# Quadcopter.net
KiCad netlist of a schematic drawn in Altium Designer
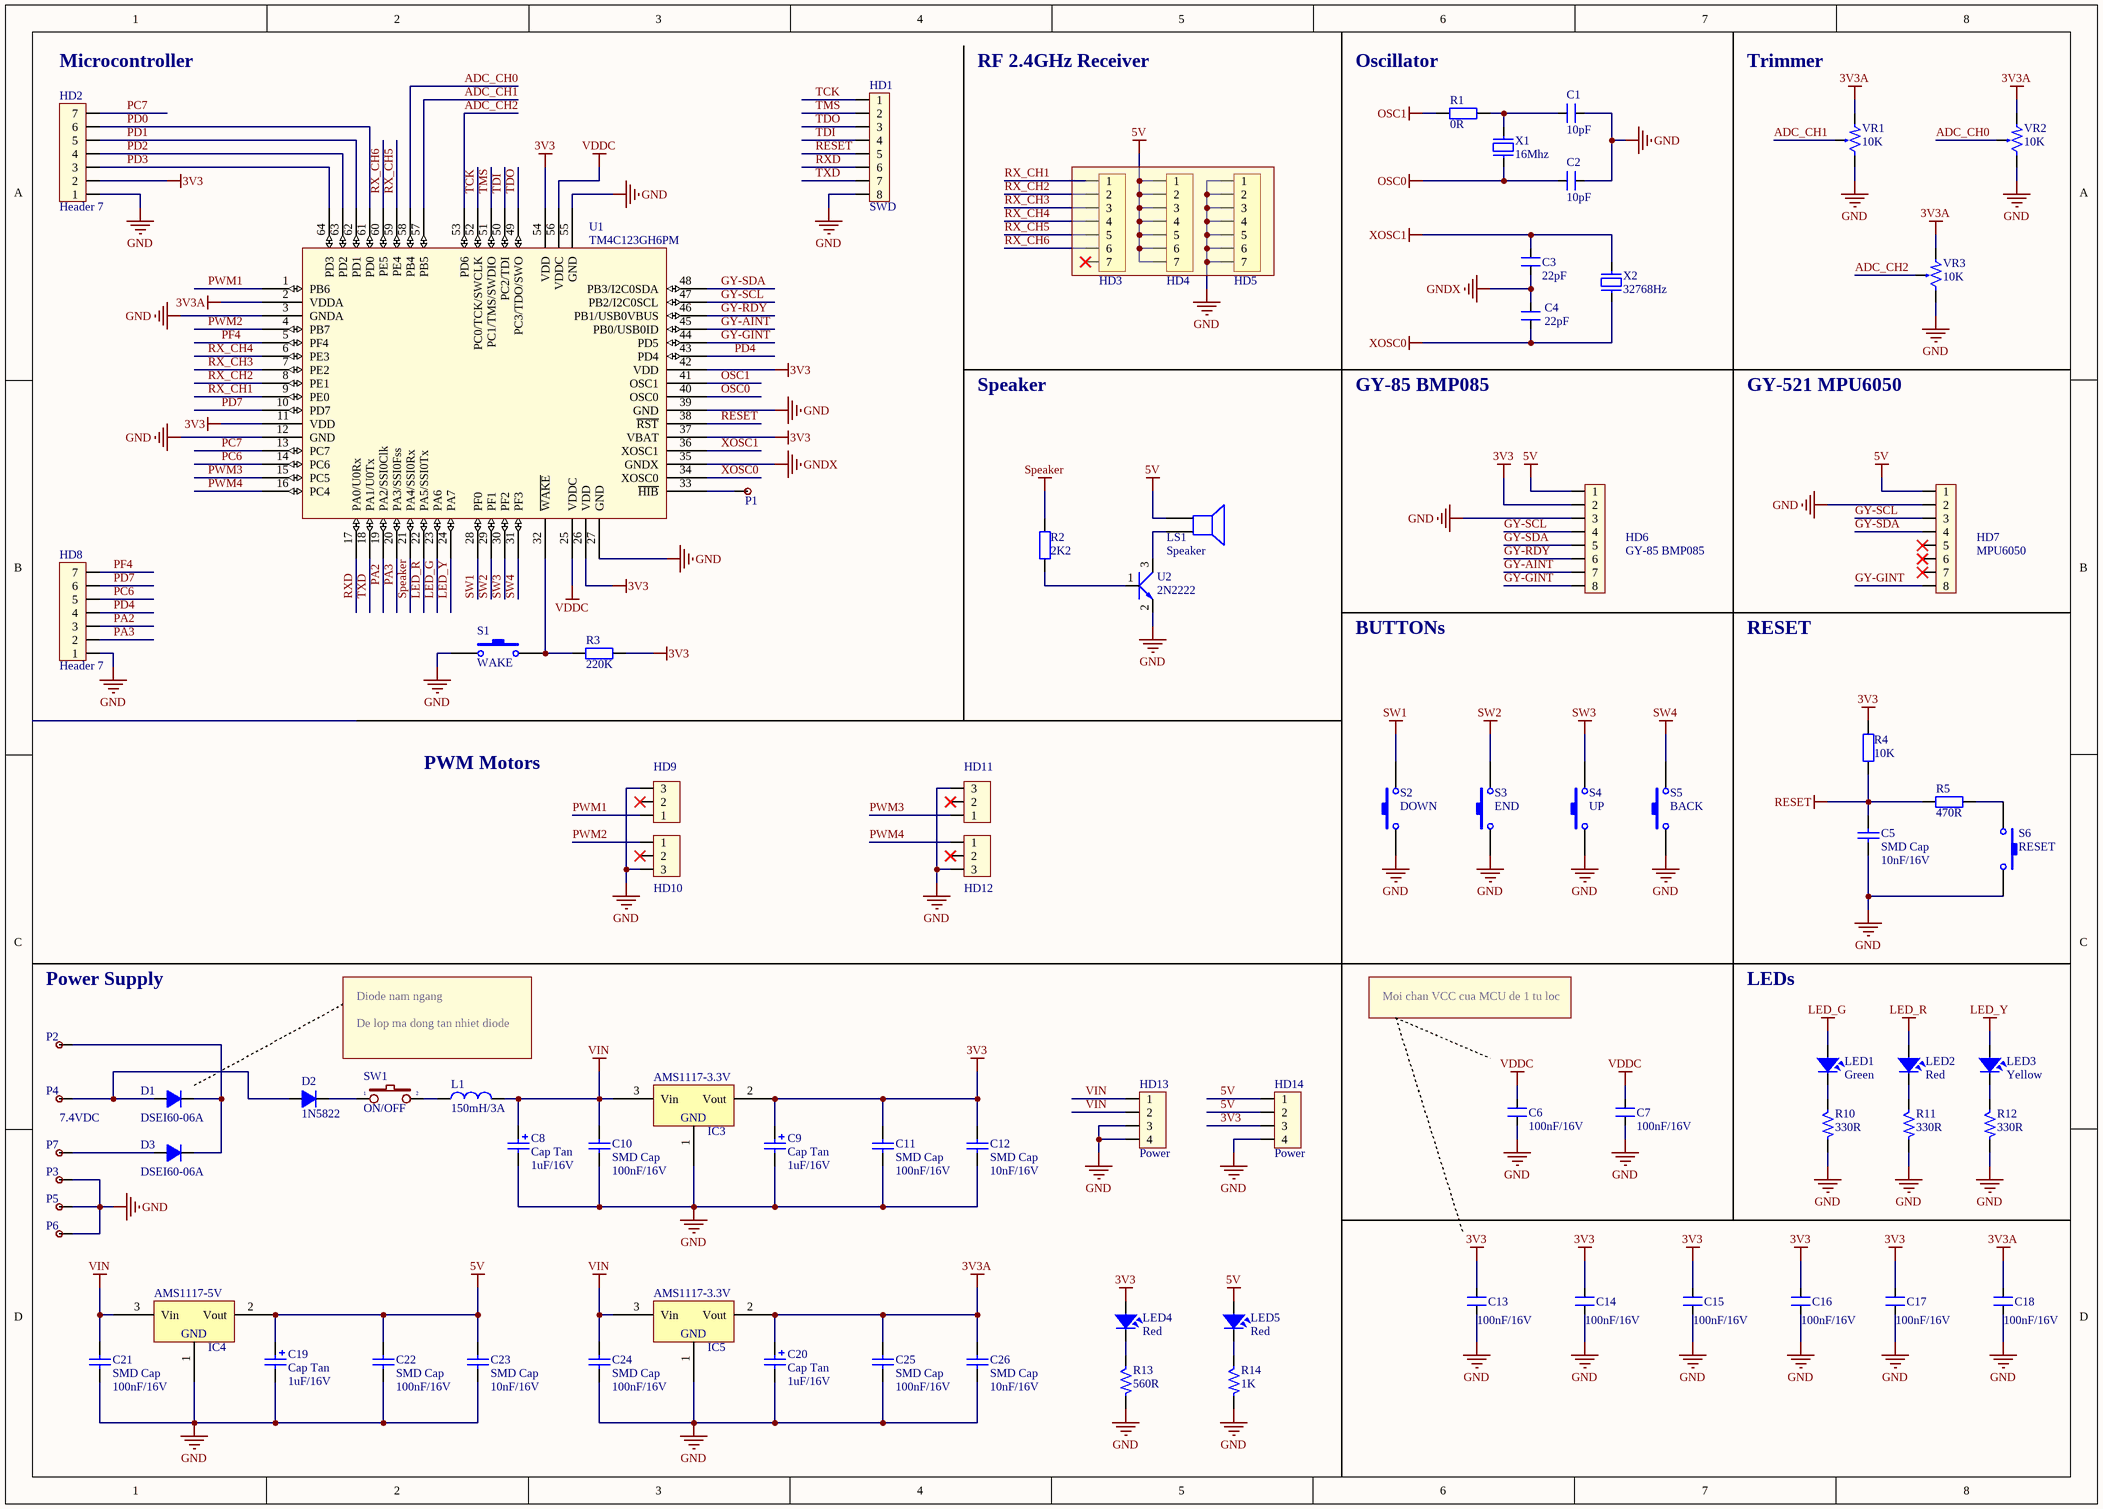
[diagram p0: Quadcopter.schdoc]

(export (version "E")
  (design (tool "Eeschema 10.0.6"))
  (components
    (comp (ref "C1")
      (value "10pF")
      (footprint "C0603")
      (description "0805-SMD Capacitor")
      (libsource (lib "syhaunguyen") (part "CN1"))
    )
    (comp (ref "C2")
      (value "10pF")
      (footprint "C0603")
      (description "0805-SMD Capacitor")
      (libsource (lib "syhaunguyen") (part "CN1"))
    )
    (comp (ref "C3")
      (value "22pF")
      (footprint "C0603")
      (description "0805-SMD Capacitor")
      (libsource (lib "syhaunguyen") (part "CN1"))
    )
    (comp (ref "C4")
      (value "22pF")
      (footprint "C0603")
      (description "0805-SMD Capacitor")
      (libsource (lib "syhaunguyen") (part "CN1"))
    )
    (comp (ref "C5")
      (value "SMD Cap")
      (footprint "C0603")
      (description "0805-10nF-50V Cap")
      (fields (field (name "ALTIUM_VALUE") "10nF/16V"))
      (libsource (lib "Miscellaneous Devices") (part "Cap"))
    )
    (comp (ref "C6")
      (value "100nF/16V")
      (footprint "C0603")
      (description "0805-SMD Capacitor")
      (fields (field (name "Comment") "SMD Cap"))
      (libsource (lib "syhaunguyen") (part "CN1"))
    )
    (comp (ref "C7")
      (value "100nF/16V")
      (footprint "C0603")
      (description "0805-SMD Capacitor")
      (fields (field (name "Comment") "SMD Cap"))
      (libsource (lib "syhaunguyen") (part "CN1"))
    )
    (comp (ref "C8")
      (value "Cap Tan")
      (footprint "CAP_TANTA_1uF_16V")
      (description "Cap Tantalum")
      (fields (field (name "ALTIUM_VALUE") "1uF/16V"))
      (libsource (lib "PassiveComponents_Sau") (part "Cap Pol2"))
    )
    (comp (ref "C9")
      (value "Cap Tan")
      (footprint "CAP_TANTA_1uF_16V")
      (description "Cap Tantalum")
      (fields (field (name "ALTIUM_VALUE") "1uF/16V"))
      (libsource (lib "PassiveComponents_Sau") (part "Cap Pol2"))
    )
    (comp (ref "C10")
      (value "SMD Cap")
      (footprint "C0603")
      (description "SMD Capacitor")
      (fields (field (name "ALTIUM_VALUE") "100nF/16V"))
      (libsource (lib "PassiveComponents_Sau") (part "Cap Cera"))
    )
    (comp (ref "C11")
      (value "SMD Cap")
      (footprint "C0603")
      (description "SMD Capacitor")
      (fields (field (name "ALTIUM_VALUE") "100nF/16V"))
      (libsource (lib "PassiveComponents_Sau") (part "Cap Cera"))
    )
    (comp (ref "C12")
      (value "SMD Cap")
      (footprint "C0603")
      (description "SMD Capacitor")
      (fields (field (name "ALTIUM_VALUE") "10nF/16V"))
      (libsource (lib "PassiveComponents_Sau") (part "Cap Cera"))
    )
    (comp (ref "C13")
      (value "100nF/16V")
      (footprint "C0603")
      (description "0805-SMD Capacitor")
      (fields (field (name "Comment") "SMD Cap"))
      (libsource (lib "syhaunguyen") (part "CN1"))
    )
    (comp (ref "C14")
      (value "100nF/16V")
      (footprint "C0603")
      (description "0805-SMD Capacitor")
      (fields (field (name "Comment") "SMD Cap"))
      (libsource (lib "syhaunguyen") (part "CN1"))
    )
    (comp (ref "C15")
      (value "100nF/16V")
      (footprint "C0603")
      (description "0805-SMD Capacitor")
      (fields (field (name "Comment") "SMD Cap"))
      (libsource (lib "syhaunguyen") (part "CN1"))
    )
    (comp (ref "C16")
      (value "100nF/16V")
      (footprint "C0603")
      (description "0805-SMD Capacitor")
      (fields (field (name "Comment") "SMD Cap"))
      (libsource (lib "syhaunguyen") (part "CN1"))
    )
    (comp (ref "C17")
      (value "100nF/16V")
      (footprint "C0603")
      (description "0805-SMD Capacitor")
      (fields (field (name "Comment") "SMD Cap"))
      (libsource (lib "syhaunguyen") (part "CN1"))
    )
    (comp (ref "C18")
      (value "100nF/16V")
      (footprint "C0603")
      (description "0805-SMD Capacitor")
      (fields (field (name "Comment") "SMD Cap"))
      (libsource (lib "syhaunguyen") (part "CN1"))
    )
    (comp (ref "C19")
      (value "Cap Tan")
      (footprint "CAP_TANTA_1uF_16V")
      (description "Cap Tantalum")
      (fields (field (name "ALTIUM_VALUE") "1uF/16V"))
      (libsource (lib "PassiveComponents_Sau") (part "Cap Pol2"))
    )
    (comp (ref "C20")
      (value "Cap Tan")
      (footprint "CAP_TANTA_1uF_16V")
      (description "Cap Tantalum")
      (fields (field (name "ALTIUM_VALUE") "1uF/16V"))
      (libsource (lib "PassiveComponents_Sau") (part "Cap Pol2"))
    )
    (comp (ref "C21")
      (value "SMD Cap")
      (footprint "C0603")
      (description "SMD Capacitor")
      (fields (field (name "ALTIUM_VALUE") "100nF/16V"))
      (libsource (lib "PassiveComponents_Sau") (part "Cap Cera"))
    )
    (comp (ref "C22")
      (value "SMD Cap")
      (footprint "C0603")
      (description "SMD Capacitor")
      (fields (field (name "ALTIUM_VALUE") "100nF/16V"))
      (libsource (lib "PassiveComponents_Sau") (part "Cap Cera"))
    )
    (comp (ref "C23")
      (value "SMD Cap")
      (footprint "C0603")
      (description "SMD Capacitor")
      (fields (field (name "ALTIUM_VALUE") "10nF/16V"))
      (libsource (lib "PassiveComponents_Sau") (part "Cap Cera"))
    )
    (comp (ref "C24")
      (value "SMD Cap")
      (footprint "C0603")
      (description "SMD Capacitor")
      (fields (field (name "ALTIUM_VALUE") "100nF/16V"))
      (libsource (lib "PassiveComponents_Sau") (part "Cap Cera"))
    )
    (comp (ref "C25")
      (value "SMD Cap")
      (footprint "C0603")
      (description "SMD Capacitor")
      (fields (field (name "ALTIUM_VALUE") "100nF/16V"))
      (libsource (lib "PassiveComponents_Sau") (part "Cap Cera"))
    )
    (comp (ref "C26")
      (value "SMD Cap")
      (footprint "C0603")
      (description "SMD Capacitor")
      (fields (field (name "ALTIUM_VALUE") "10nF/16V"))
      (libsource (lib "PassiveComponents_Sau") (part "Cap Cera"))
    )
    (comp (ref "D1")
      (value "DSEI60-06A")
      (footprint "DSEI60-06A_STAND")
      (description "Diode 60A")
      (libsource (lib "VNELEK") (part "D1A"))
    )
    (comp (ref "D2")
      (value "1N5822")
      (footprint "1N5822")
      (description "Diode  3A")
      (libsource (lib "VNELEK") (part "D1A"))
    )
    (comp (ref "D3")
      (value "DSEI60-06A")
      (footprint "DSEI60-06A_STAND")
      (description "Diode 60A")
      (libsource (lib "VNELEK") (part "D1A"))
    )
    (comp (ref "HD1")
      (value "SWD")
      (footprint "Header_8")
      (description "Hedear 8")
      (fields (field (name "CREAT BY") "VanDungEvn@Gmail.com"))
      (libsource (lib "VNELEK") (part "Hed8"))
    )
    (comp (ref "HD2") (value "Header 7") (footprint "Header_7") (libsource (lib "") (part "Hed7_1")))
    (comp (ref "HD3") (value "Header 7") (footprint "Header_7") (libsource (lib "Tran Tuan") (part "Hed7")))
    (comp (ref "HD4") (value "Header 7") (footprint "Header_7") (libsource (lib "Tran Tuan") (part "Hed7")))
    (comp (ref "HD5") (value "Header 7") (footprint "Header_7") (libsource (lib "Tran Tuan") (part "Hed7")))
    (comp (ref "HD6")
      (value "GY-85 BMP085")
      (footprint "Header_8")
      (description "Hedear 8")
      (fields (field (name "CREAT BY") "VanDungEvn@Gmail.com"))
      (libsource (lib "VNELEK") (part "Hed8"))
    )
    (comp (ref "HD7")
      (value "MPU6050")
      (footprint "Header_8")
      (description "Hedear 8")
      (fields (field (name "CREAT BY") "VanDungEvn@Gmail.com"))
      (libsource (lib "VNELEK") (part "Hed8"))
    )
    (comp (ref "HD8") (value "Header 7") (footprint "Header_7") (libsource (lib "") (part "Hed7_1")))
    (comp (ref "HD9")
      (value "Header 3")
      (footprint "JP3H_NAM")
      (description "Header 3 (Green)")
      (libsource (lib "VNELEK") (part "Hed3"))
    )
    (comp (ref "HD10")
      (value "Header 3")
      (footprint "JP3H_NAM")
      (description "Header 3 (Green)")
      (libsource (lib "") (part "Hed3_1"))
    )
    (comp (ref "HD11")
      (value "Header 3")
      (footprint "JP3H_NAM")
      (description "Header 3 (Green)")
      (libsource (lib "VNELEK") (part "Hed3"))
    )
    (comp (ref "HD12")
      (value "Header 3")
      (footprint "JP3H_NAM")
      (description "Header 3 (Green)")
      (libsource (lib "") (part "Hed3_1"))
    )
    (comp (ref "HD13")
      (value "Power")
      (footprint "Header_4")
      (description "Header 4 (Green)")
      (libsource (lib "VNELEK") (part "Hed4"))
    )
    (comp (ref "HD14")
      (value "Power")
      (footprint "Header_4")
      (description "Header 4 (Green)")
      (libsource (lib "VNELEK") (part "Hed4"))
    )
    (comp (ref "IC3")
      (value "AMS1117-3.3V")
      (footprint "AMS1117-5.0V")
      (libsource (lib "LuanVanPIR") (part "AMS1117"))
    )
    (comp (ref "IC4")
      (value "AMS1117-5V")
      (footprint "AMS1117-5.0V")
      (libsource (lib "LuanVanPIR") (part "AMS1117"))
    )
    (comp (ref "IC5")
      (value "AMS1117-3.3V")
      (footprint "AMS1117-5.0V")
      (libsource (lib "LuanVanPIR") (part "AMS1117"))
    )
    (comp (ref "L1")
      (value "150mH/3A")
      (footprint "Inductor 150mH,3A")
      (description "Inductor")
      (libsource (lib "VNELEK") (part "L1"))
    )
    (comp (ref "LED1")
      (value "Green")
      (footprint "Led 0805G")
      (description "LED Single colour Green and Red")
      (libsource (lib "VNELEK") (part "LED"))
    )
    (comp (ref "LED2")
      (value "Red")
      (footprint "Led 0805R")
      (description "LED Single colour Green and Red")
      (libsource (lib "VNELEK") (part "LED"))
    )
    (comp (ref "LED3")
      (value "Yellow")
      (footprint "Led 0805Y")
      (description "LED Single colour Green and Red")
      (libsource (lib "VNELEK") (part "LED"))
    )
    (comp (ref "LED4")
      (value "Red")
      (footprint "Led 0805R")
      (description "LED Single colour Green and Red")
      (libsource (lib "VNELEK") (part "LED"))
    )
    (comp (ref "LED5")
      (value "Red")
      (footprint "Led 0805R")
      (description "LED Single colour Green and Red")
      (libsource (lib "VNELEK") (part "LED"))
    )
    (comp (ref "LS1")
      (value "Speaker")
      (footprint "SPEAKER")
      (description "Loudspeaker")
      (fields (field (name "PUBLISHER") "Altium Limited"))
      (libsource (lib "Miscellaneous Devices") (part "Speaker"))
    )
    (comp (ref "P1") (value "Pad") (footprint "TP1") (libsource (lib "Tran Tuan") (part "Pad")))
    (comp (ref "P2") (value "Pad") (footprint "TP1") (libsource (lib "Tran Tuan") (part "Pad")))
    (comp (ref "P3") (value "Pad") (footprint "TP1") (libsource (lib "Tran Tuan") (part "Pad")))
    (comp (ref "P4") (value "Pad") (footprint "TP1") (libsource (lib "Tran Tuan") (part "Pad")))
    (comp (ref "P5") (value "Pad") (footprint "TP1") (libsource (lib "Tran Tuan") (part "Pad")))
    (comp (ref "P6") (value "Pad") (footprint "TP1") (libsource (lib "Tran Tuan") (part "Pad")))
    (comp (ref "P7") (value "Pad") (footprint "TP1") (libsource (lib "Tran Tuan") (part "Pad")))
    (comp (ref "R1")
      (value "0R")
      (footprint "RESC2012L")
      (description "Resistor")
      (fields (field (name "Comment") "Res2") (field (name "PUBLISHER") "Altium Limited"))
      (libsource (lib "") (part "Res2_3"))
    )
    (comp (ref "R2")
      (value "2K2")
      (footprint "RESC2012L")
      (description "Resistor")
      (fields (field (name "Comment") "Res2") (field (name "PUBLISHER") "Altium Limited"))
      (libsource (lib "") (part "Res2_2"))
    )
    (comp (ref "R3")
      (value "220K")
      (footprint "RESC2012L")
      (description "Resistor")
      (fields (field (name "Comment") "Res2") (field (name "PUBLISHER") "Altium Limited"))
      (libsource (lib "") (part "Res2_1"))
    )
    (comp (ref "R4")
      (value "10K")
      (footprint "RESC2012L")
      (description "Resistor")
      (fields (field (name "Comment") "Res2") (field (name "PUBLISHER") "Altium Limited"))
      (libsource (lib "Miscellaneous Devices") (part "Res2"))
    )
    (comp (ref "R5")
      (value "470R")
      (footprint "RESC2012L")
      (description "Resistor")
      (fields (field (name "Comment") "Res2") (field (name "PUBLISHER") "Altium Limited"))
      (libsource (lib "") (part "Res2_1"))
    )
    (comp (ref "R10")
      (value "330R")
      (footprint "RESC2012L")
      (description "Resistor 1/4W")
      (libsource (lib "VNELEK") (part "R"))
    )
    (comp (ref "R11")
      (value "330R")
      (footprint "RESC2012L")
      (description "Resistor 1/4W")
      (libsource (lib "VNELEK") (part "R"))
    )
    (comp (ref "R12")
      (value "330R")
      (footprint "RESC2012L")
      (description "Resistor 1/4W")
      (libsource (lib "VNELEK") (part "R"))
    )
    (comp (ref "R13")
      (value "560R")
      (footprint "RESC2012L")
      (description "Resistor 1/4W")
      (libsource (lib "VNELEK") (part "R"))
    )
    (comp (ref "R14")
      (value "1K")
      (footprint "RESC2012L")
      (description "Resistor 1/4W")
      (libsource (lib "VNELEK") (part "R"))
    )
    (comp (ref "S1")
      (value "WAKE")
      (footprint "BUTTON 2PIN TRON")
      (description "Switch")
      (fields (field (name "PUBLISHER") "Altium Limited"))
      (libsource (lib "Miscellaneous Devices") (part "SW-PB"))
    )
    (comp (ref "S2")
      (value "DOWN")
      (footprint "BUTTON 2PIN TRON")
      (description "Switch")
      (fields (field (name "PUBLISHER") "Altium Limited"))
      (libsource (lib "Miscellaneous Devices") (part "SW-PB"))
    )
    (comp (ref "S3")
      (value "END")
      (footprint "BUTTON 2PIN TRON")
      (description "Switch")
      (fields (field (name "PUBLISHER") "Altium Limited"))
      (libsource (lib "Miscellaneous Devices") (part "SW-PB"))
    )
    (comp (ref "S4")
      (value "UP")
      (footprint "BUTTON 2PIN TRON")
      (description "Switch")
      (fields (field (name "PUBLISHER") "Altium Limited"))
      (libsource (lib "Miscellaneous Devices") (part "SW-PB"))
    )
    (comp (ref "S5")
      (value "BACK")
      (footprint "BUTTON 2PIN TRON")
      (description "Switch")
      (fields (field (name "PUBLISHER") "Altium Limited"))
      (libsource (lib "Miscellaneous Devices") (part "SW-PB"))
    )
    (comp (ref "S6")
      (value "RESET")
      (footprint "BUTTON 2PIN TRON")
      (description "Switch")
      (fields (field (name "PUBLISHER") "Altium Limited"))
      (libsource (lib "Miscellaneous Devices") (part "SW-PB"))
    )
    (comp (ref "SW1")
      (value "ON/OFF")
      (footprint "CKCD11-101")
      (description "Switch button 2 pin")
      (libsource (lib "VNELEK") (part "SW2"))
    )
    (comp (ref "U1")
      (value "TM4C123GH6PM")
      (footprint "TM4C123GH6PM")
      (description "Tiva C Series Microcontroller")
      (libsource (lib "Tran Tuan") (part "TM4C123GH6PM"))
    )
    (comp (ref "U2")
      (value "2N2222")
      (footprint "MMBT2222A")
      (description "NPN switching transistors")
      (libsource (lib "Tran Tuan") (part "2N2222"))
    )
    (comp (ref "VR1")
      (value "10K")
      (footprint "VR")
      (description "Var Resistor")
      (libsource (lib "VNELEK") (part "VR1"))
    )
    (comp (ref "VR2")
      (value "10K")
      (footprint "VR")
      (description "Var Resistor")
      (libsource (lib "VNELEK") (part "VR1"))
    )
    (comp (ref "VR3")
      (value "10K")
      (footprint "VR")
      (description "Var Resistor")
      (libsource (lib "VNELEK") (part "VR1"))
    )
    (comp (ref "X1")
      (value "16Mhz")
      (footprint "CSTCE16M0V53-R0")
      (description "Crystal For all Crystal 2pin.")
      (libsource (lib "syhaunguyen") (part "XT2"))
    )
    (comp (ref "X2")
      (value "32768Hz")
      (footprint "32.678 Khz")
      (description "Crystal For all Crystal 2pin.")
      (libsource (lib "syhaunguyen") (part "XT2"))
    )
  )
  (nets
    (net (code "1") (name "/ADC_CH0") (class "Default")
      (node (ref "U1") (pin "58") (pinfunction "PB4_58") (pintype "bidirectional"))
      (node (ref "VR2") (pin "2") (pinfunction "2_2") (pintype "passive"))
    )
    (net (code "2") (name "/ADC_CH1") (class "Default")
      (node (ref "U1") (pin "57") (pinfunction "PB5_57") (pintype "bidirectional"))
      (node (ref "VR1") (pin "2") (pinfunction "2_2") (pintype "passive"))
    )
    (net (code "3") (name "/ADC_CH2") (class "Default")
      (node (ref "U1") (pin "53") (pinfunction "PD6_53") (pintype "bidirectional"))
      (node (ref "VR3") (pin "2") (pinfunction "2_2") (pintype "passive"))
    )
    (net (code "4") (name "/GY-AINT") (class "Default")
      (node (ref "HD6") (pin "7") (pinfunction "7_7") (pintype "passive"))
      (node (ref "U1") (pin "45") (pinfunction "PB0/USB0ID_45") (pintype "bidirectional"))
    )
    (net (code "5") (name "/GY-GINT") (class "Default")
      (node (ref "HD6") (pin "8") (pinfunction "8_8") (pintype "passive"))
      (node (ref "HD7") (pin "8") (pinfunction "8_8") (pintype "passive"))
      (node (ref "U1") (pin "44") (pinfunction "PD5_44") (pintype "bidirectional"))
    )
    (net (code "6") (name "/GY-RDY") (class "Default")
      (node (ref "HD6") (pin "6") (pinfunction "6_6") (pintype "passive"))
      (node (ref "U1") (pin "46") (pinfunction "PB1/USB0VBUS_46") (pintype "bidirectional"))
    )
    (net (code "7") (name "/GY-SCL") (class "Default")
      (node (ref "HD6") (pin "4") (pinfunction "4_4") (pintype "passive"))
      (node (ref "HD7") (pin "3") (pinfunction "3_3") (pintype "passive"))
      (node (ref "U1") (pin "47") (pinfunction "PB2/I2C0SCL_47") (pintype "bidirectional"))
    )
    (net (code "8") (name "/GY-SDA") (class "Default")
      (node (ref "HD6") (pin "5") (pinfunction "5_5") (pintype "passive"))
      (node (ref "HD7") (pin "4") (pinfunction "4_4") (pintype "passive"))
      (node (ref "U1") (pin "48") (pinfunction "PB3/I2C0SDA_48") (pintype "bidirectional"))
    )
    (net (code "9") (name "/PA2") (class "Default")
      (node (ref "HD8") (pin "3") (pinfunction "3_3") (pintype "passive"))
      (node (ref "U1") (pin "19") (pinfunction "PA2/SSI0Clk_19") (pintype "bidirectional"))
    )
    (net (code "10") (name "/PA3") (class "Default")
      (node (ref "HD8") (pin "2") (pinfunction "2_2") (pintype "passive"))
      (node (ref "U1") (pin "20") (pinfunction "PA3/SSI0Fss_20") (pintype "bidirectional"))
    )
    (net (code "11") (name "/PC6") (class "Default")
      (node (ref "HD8") (pin "5") (pinfunction "5_5") (pintype "passive"))
      (node (ref "U1") (pin "14") (pinfunction "PC6_14") (pintype "bidirectional"))
    )
    (net (code "12") (name "/PC7") (class "Default")
      (node (ref "HD2") (pin "7") (pinfunction "7_7") (pintype "passive"))
      (node (ref "U1") (pin "13") (pinfunction "PC7_13") (pintype "bidirectional"))
    )
    (net (code "13") (name "/PD0") (class "Default")
      (node (ref "HD2") (pin "6") (pinfunction "6_6") (pintype "passive"))
      (node (ref "U1") (pin "61") (pinfunction "PD0_61") (pintype "bidirectional"))
    )
    (net (code "14") (name "/PD1") (class "Default")
      (node (ref "HD2") (pin "5") (pinfunction "5_5") (pintype "passive"))
      (node (ref "U1") (pin "62") (pinfunction "PD1_62") (pintype "bidirectional"))
    )
    (net (code "15") (name "/PD2") (class "Default")
      (node (ref "HD2") (pin "4") (pinfunction "4_4") (pintype "passive"))
      (node (ref "U1") (pin "63") (pinfunction "PD2_63") (pintype "bidirectional"))
    )
    (net (code "16") (name "/PD3") (class "Default")
      (node (ref "HD2") (pin "3") (pinfunction "3_3") (pintype "passive"))
      (node (ref "U1") (pin "64") (pinfunction "PD3_64") (pintype "bidirectional"))
    )
    (net (code "17") (name "/PD4") (class "Default")
      (node (ref "HD8") (pin "4") (pinfunction "4_4") (pintype "passive"))
      (node (ref "U1") (pin "43") (pinfunction "PD4_43") (pintype "bidirectional"))
    )
    (net (code "18") (name "/PD7") (class "Default")
      (node (ref "HD8") (pin "6") (pinfunction "6_6") (pintype "passive"))
      (node (ref "U1") (pin "10") (pinfunction "PD7_10") (pintype "bidirectional"))
    )
    (net (code "19") (name "/PF4") (class "Default")
      (node (ref "HD8") (pin "7") (pinfunction "7_7") (pintype "passive"))
      (node (ref "U1") (pin "5") (pinfunction "PF4_5") (pintype "bidirectional"))
    )
    (net (code "20") (name "/PWM1") (class "Default")
      (node (ref "HD9") (pin "1") (pinfunction "1_1") (pintype "passive"))
      (node (ref "U1") (pin "1") (pinfunction "PB6_1") (pintype "bidirectional"))
    )
    (net (code "21") (name "/PWM2") (class "Default")
      (node (ref "HD10") (pin "1") (pinfunction "1_1") (pintype "passive"))
      (node (ref "U1") (pin "4") (pinfunction "PB7_4") (pintype "bidirectional"))
    )
    (net (code "22") (name "/PWM3") (class "Default")
      (node (ref "HD11") (pin "1") (pinfunction "1_1") (pintype "passive"))
      (node (ref "U1") (pin "15") (pinfunction "PC5_15") (pintype "bidirectional"))
    )
    (net (code "23") (name "/PWM4") (class "Default")
      (node (ref "HD12") (pin "1") (pinfunction "1_1") (pintype "passive"))
      (node (ref "U1") (pin "16") (pinfunction "PC4_16") (pintype "bidirectional"))
    )
    (net (code "24") (name "/RXD") (class "Default")
      (node (ref "HD1") (pin "6") (pinfunction "6_6") (pintype "passive"))
      (node (ref "U1") (pin "17") (pinfunction "PA0/U0Rx_17") (pintype "bidirectional"))
    )
    (net (code "25") (name "/RX_CH1") (class "Default")
      (node (ref "HD3") (pin "1") (pinfunction "1_1") (pintype "passive"))
      (node (ref "U1") (pin "9") (pinfunction "PE0_9") (pintype "bidirectional"))
    )
    (net (code "26") (name "/RX_CH2") (class "Default")
      (node (ref "HD3") (pin "2") (pinfunction "2_2") (pintype "passive"))
      (node (ref "U1") (pin "8") (pinfunction "PE1_8") (pintype "bidirectional"))
    )
    (net (code "27") (name "/RX_CH3") (class "Default")
      (node (ref "HD3") (pin "3") (pinfunction "3_3") (pintype "passive"))
      (node (ref "U1") (pin "7") (pinfunction "PE2_7") (pintype "bidirectional"))
    )
    (net (code "28") (name "/RX_CH4") (class "Default")
      (node (ref "HD3") (pin "4") (pinfunction "4_4") (pintype "passive"))
      (node (ref "U1") (pin "6") (pinfunction "PE3_6") (pintype "bidirectional"))
    )
    (net (code "29") (name "/RX_CH5") (class "Default")
      (node (ref "HD3") (pin "5") (pinfunction "5_5") (pintype "passive"))
      (node (ref "U1") (pin "59") (pinfunction "PE4_59") (pintype "bidirectional"))
    )
    (net (code "30") (name "/RX_CH6") (class "Default")
      (node (ref "HD3") (pin "6") (pinfunction "6_6") (pintype "passive"))
      (node (ref "U1") (pin "60") (pinfunction "PE5_60") (pintype "bidirectional"))
    )
    (net (code "31") (name "/TCK") (class "Default")
      (node (ref "HD1") (pin "1") (pinfunction "1_1") (pintype "passive"))
      (node (ref "U1") (pin "52") (pinfunction "PC0/TCK/SWCLK_52") (pintype "bidirectional"))
    )
    (net (code "32") (name "/TDI") (class "Default")
      (node (ref "HD1") (pin "4") (pinfunction "4_4") (pintype "passive"))
      (node (ref "U1") (pin "50") (pinfunction "PC2/TDI_50") (pintype "bidirectional"))
    )
    (net (code "33") (name "/TDO") (class "Default")
      (node (ref "HD1") (pin "3") (pinfunction "3_3") (pintype "passive"))
      (node (ref "U1") (pin "49") (pinfunction "PC3/TDO/SWO_49") (pintype "bidirectional"))
    )
    (net (code "34") (name "/TMS") (class "Default")
      (node (ref "HD1") (pin "2") (pinfunction "2_2") (pintype "passive"))
      (node (ref "U1") (pin "51") (pinfunction "PC1/TMS/SWDIO_51") (pintype "bidirectional"))
    )
    (net (code "35") (name "/TXD") (class "Default")
      (node (ref "HD1") (pin "7") (pinfunction "7_7") (pintype "passive"))
      (node (ref "U1") (pin "18") (pinfunction "PA1/U0Tx_18") (pintype "bidirectional"))
    )
    (net (code "36") (name "3V3") (class "Default")
      (node (ref "C11") (pin "2") (pinfunction "2_2") (pintype "passive"))
      (node (ref "C12") (pin "2") (pinfunction "2_2") (pintype "passive"))
      (node (ref "C13") (pin "1") (pinfunction "1_1") (pintype "passive"))
      (node (ref "C14") (pin "1") (pinfunction "1_1") (pintype "passive"))
      (node (ref "C15") (pin "1") (pinfunction "1_1") (pintype "passive"))
      (node (ref "C16") (pin "1") (pinfunction "1_1") (pintype "passive"))
      (node (ref "C17") (pin "1") (pinfunction "1_1") (pintype "passive"))
      (node (ref "C9") (pin "1") (pinfunction "+_1") (pintype "passive"))
      (node (ref "HD14") (pin "3") (pinfunction "3_3") (pintype "passive"))
      (node (ref "HD2") (pin "2") (pinfunction "2_2") (pintype "passive"))
      (node (ref "HD6") (pin "2") (pinfunction "2_2") (pintype "passive"))
      (node (ref "IC3") (pin "2") (pinfunction "Vout_2") (pintype "passive"))
      (node (ref "LED4") (pin "1") (pinfunction "1_1") (pintype "passive"))
      (node (ref "R3") (pin "1") (pinfunction "1_1") (pintype "passive"))
      (node (ref "R4") (pin "2") (pinfunction "2_2") (pintype "passive"))
      (node (ref "U1") (pin "11") (pinfunction "VDD_11") (pintype "power_in"))
      (node (ref "U1") (pin "26") (pinfunction "VDD_26") (pintype "power_in"))
      (node (ref "U1") (pin "37") (pinfunction "VBAT_37") (pintype "power_in"))
      (node (ref "U1") (pin "42") (pinfunction "VDD_42") (pintype "power_in"))
      (node (ref "U1") (pin "54") (pinfunction "VDD_54") (pintype "power_in"))
    )
    (net (code "37") (name "3V3A") (class "Default")
      (node (ref "C18") (pin "1") (pinfunction "1_1") (pintype "passive"))
      (node (ref "C20") (pin "1") (pinfunction "+_1") (pintype "passive"))
      (node (ref "C25") (pin "2") (pinfunction "2_2") (pintype "passive"))
      (node (ref "C26") (pin "2") (pinfunction "2_2") (pintype "passive"))
      (node (ref "IC5") (pin "2") (pinfunction "Vout_2") (pintype "passive"))
      (node (ref "U1") (pin "2") (pinfunction "VDDA_2") (pintype "power_in"))
      (node (ref "VR1") (pin "1") (pinfunction "1_1") (pintype "passive"))
      (node (ref "VR2") (pin "1") (pinfunction "1_1") (pintype "passive"))
      (node (ref "VR3") (pin "1") (pinfunction "1_1") (pintype "passive"))
    )
    (net (code "38") (name "5V") (class "Default")
      (node (ref "C19") (pin "1") (pinfunction "+_1") (pintype "passive"))
      (node (ref "C22") (pin "2") (pinfunction "2_2") (pintype "passive"))
      (node (ref "C23") (pin "2") (pinfunction "2_2") (pintype "passive"))
      (node (ref "HD14") (pin "1") (pinfunction "1_1") (pintype "passive"))
      (node (ref "HD14") (pin "2") (pinfunction "2_2") (pintype "passive"))
      (node (ref "HD4") (pin "1") (pinfunction "1_1") (pintype "passive"))
      (node (ref "HD4") (pin "2") (pinfunction "2_2") (pintype "passive"))
      (node (ref "HD4") (pin "3") (pinfunction "3_3") (pintype "passive"))
      (node (ref "HD4") (pin "4") (pinfunction "4_4") (pintype "passive"))
      (node (ref "HD4") (pin "5") (pinfunction "5_5") (pintype "passive"))
      (node (ref "HD4") (pin "6") (pinfunction "6_6") (pintype "passive"))
      (node (ref "HD4") (pin "7") (pinfunction "7_7") (pintype "passive"))
      (node (ref "HD6") (pin "1") (pinfunction "1_1") (pintype "passive"))
      (node (ref "HD7") (pin "1") (pinfunction "1_1") (pintype "passive"))
      (node (ref "IC4") (pin "2") (pinfunction "Vout_2") (pintype "passive"))
      (node (ref "LED5") (pin "1") (pinfunction "1_1") (pintype "passive"))
      (node (ref "LS1") (pin "2") (pinfunction "2_2") (pintype "passive"))
    )
    (net (code "39") (name "GND") (class "Default")
      (node (ref "C1") (pin "1") (pinfunction "1_1") (pintype "passive"))
      (node (ref "C10") (pin "1") (pinfunction "1_1") (pintype "passive"))
      (node (ref "C11") (pin "1") (pinfunction "1_1") (pintype "passive"))
      (node (ref "C12") (pin "1") (pinfunction "1_1") (pintype "passive"))
      (node (ref "C13") (pin "2") (pinfunction "2_2") (pintype "passive"))
      (node (ref "C14") (pin "2") (pinfunction "2_2") (pintype "passive"))
      (node (ref "C15") (pin "2") (pinfunction "2_2") (pintype "passive"))
      (node (ref "C16") (pin "2") (pinfunction "2_2") (pintype "passive"))
      (node (ref "C17") (pin "2") (pinfunction "2_2") (pintype "passive"))
      (node (ref "C18") (pin "2") (pinfunction "2_2") (pintype "passive"))
      (node (ref "C19") (pin "2") (pinfunction "-_2") (pintype "passive"))
      (node (ref "C2") (pin "1") (pinfunction "1_1") (pintype "passive"))
      (node (ref "C20") (pin "2") (pinfunction "-_2") (pintype "passive"))
      (node (ref "C21") (pin "1") (pinfunction "1_1") (pintype "passive"))
      (node (ref "C22") (pin "1") (pinfunction "1_1") (pintype "passive"))
      (node (ref "C23") (pin "1") (pinfunction "1_1") (pintype "passive"))
      (node (ref "C24") (pin "1") (pinfunction "1_1") (pintype "passive"))
      (node (ref "C25") (pin "1") (pinfunction "1_1") (pintype "passive"))
      (node (ref "C26") (pin "1") (pinfunction "1_1") (pintype "passive"))
      (node (ref "C5") (pin "2") (pinfunction "2_2") (pintype "passive"))
      (node (ref "C6") (pin "2") (pinfunction "2_2") (pintype "passive"))
      (node (ref "C7") (pin "2") (pinfunction "2_2") (pintype "passive"))
      (node (ref "C8") (pin "2") (pinfunction "-_2") (pintype "passive"))
      (node (ref "C9") (pin "2") (pinfunction "-_2") (pintype "passive"))
      (node (ref "HD1") (pin "8") (pinfunction "8_8") (pintype "passive"))
      (node (ref "HD10") (pin "3") (pinfunction "3_3") (pintype "passive"))
      (node (ref "HD11") (pin "3") (pinfunction "3_3") (pintype "passive"))
      (node (ref "HD12") (pin "3") (pinfunction "3_3") (pintype "passive"))
      (node (ref "HD13") (pin "3") (pinfunction "3_3") (pintype "passive"))
      (node (ref "HD13") (pin "4") (pinfunction "4_4") (pintype "passive"))
      (node (ref "HD14") (pin "4") (pinfunction "4_4") (pintype "passive"))
      (node (ref "HD2") (pin "1") (pinfunction "1_1") (pintype "passive"))
      (node (ref "HD5") (pin "1") (pinfunction "1_1") (pintype "passive"))
      (node (ref "HD5") (pin "2") (pinfunction "2_2") (pintype "passive"))
      (node (ref "HD5") (pin "3") (pinfunction "3_3") (pintype "passive"))
      (node (ref "HD5") (pin "4") (pinfunction "4_4") (pintype "passive"))
      (node (ref "HD5") (pin "5") (pinfunction "5_5") (pintype "passive"))
      (node (ref "HD5") (pin "6") (pinfunction "6_6") (pintype "passive"))
      (node (ref "HD5") (pin "7") (pinfunction "7_7") (pintype "passive"))
      (node (ref "HD6") (pin "3") (pinfunction "3_3") (pintype "passive"))
      (node (ref "HD7") (pin "2") (pinfunction "2_2") (pintype "passive"))
      (node (ref "HD8") (pin "1") (pinfunction "1_1") (pintype "passive"))
      (node (ref "HD9") (pin "3") (pinfunction "3_3") (pintype "passive"))
      (node (ref "IC3") (pin "1") (pinfunction "GND_1") (pintype "passive"))
      (node (ref "IC4") (pin "1") (pinfunction "GND_1") (pintype "passive"))
      (node (ref "IC5") (pin "1") (pinfunction "GND_1") (pintype "passive"))
      (node (ref "P3") (pin "1") (pinfunction "1_1") (pintype "passive"))
      (node (ref "P5") (pin "1") (pinfunction "1_1") (pintype "passive"))
      (node (ref "P6") (pin "1") (pinfunction "1_1") (pintype "passive"))
      (node (ref "R10") (pin "2") (pinfunction "2_2") (pintype "passive"))
      (node (ref "R11") (pin "2") (pinfunction "2_2") (pintype "passive"))
      (node (ref "R12") (pin "2") (pinfunction "2_2") (pintype "passive"))
      (node (ref "R13") (pin "2") (pinfunction "2_2") (pintype "passive"))
      (node (ref "R14") (pin "2") (pinfunction "2_2") (pintype "passive"))
      (node (ref "S1") (pin "1") (pinfunction "1_1") (pintype "passive"))
      (node (ref "S2") (pin "1") (pinfunction "1_1") (pintype "passive"))
      (node (ref "S3") (pin "1") (pinfunction "1_1") (pintype "passive"))
      (node (ref "S4") (pin "1") (pinfunction "1_1") (pintype "passive"))
      (node (ref "S5") (pin "1") (pinfunction "1_1") (pintype "passive"))
      (node (ref "S6") (pin "2") (pinfunction "2_2") (pintype "passive"))
      (node (ref "U1") (pin "12") (pinfunction "GND_12") (pintype "power_in"))
      (node (ref "U1") (pin "27") (pinfunction "GND_27") (pintype "power_in"))
      (node (ref "U1") (pin "3") (pinfunction "GNDA_3") (pintype "power_in"))
      (node (ref "U1") (pin "39") (pinfunction "GND_39") (pintype "power_in"))
      (node (ref "U1") (pin "55") (pinfunction "GND_55") (pintype "power_in"))
      (node (ref "U2") (pin "2") (pinfunction "E_2") (pintype "passive"))
      (node (ref "VR1") (pin "3") (pinfunction "3_3") (pintype "passive"))
      (node (ref "VR2") (pin "3") (pinfunction "3_3") (pintype "passive"))
      (node (ref "VR3") (pin "3") (pinfunction "3_3") (pintype "passive"))
    )
    (net (code "40") (name "GNDX") (class "Default")
      (node (ref "C3") (pin "2") (pinfunction "2_2") (pintype "passive"))
      (node (ref "C4") (pin "1") (pinfunction "1_1") (pintype "passive"))
      (node (ref "U1") (pin "35") (pinfunction "GNDX_35") (pintype "power_in"))
    )
    (net (code "41") (name "LED_G") (class "Default")
      (node (ref "LED1") (pin "1") (pinfunction "1_1") (pintype "passive"))
      (node (ref "U1") (pin "23") (pinfunction "PA6_23") (pintype "bidirectional"))
    )
    (net (code "42") (name "LED_R") (class "Default")
      (node (ref "LED2") (pin "1") (pinfunction "1_1") (pintype "passive"))
      (node (ref "U1") (pin "22") (pinfunction "PA5/SSI0Tx_22") (pintype "bidirectional"))
    )
    (net (code "43") (name "LED_Y") (class "Default")
      (node (ref "LED3") (pin "1") (pinfunction "1_1") (pintype "passive"))
      (node (ref "U1") (pin "24") (pinfunction "PA7_24") (pintype "bidirectional"))
    )
    (net (code "44") (name "Net-(C1-Pad2)") (class "Default")
      (node (ref "C1") (pin "2") (pinfunction "2_2") (pintype "passive"))
      (node (ref "R1") (pin "2") (pinfunction "2_2") (pintype "passive"))
      (node (ref "X1") (pin "1") (pinfunction "1_1") (pintype "passive"))
    )
    (net (code "45") (name "Net-(D1-A)") (class "Default")
      (node (ref "D1") (pin "2") (pinfunction "A_2") (pintype "passive"))
      (node (ref "D3") (pin "2") (pinfunction "A_2") (pintype "passive"))
      (node (ref "P2") (pin "1") (pinfunction "1_1") (pintype "passive"))
    )
    (net (code "46") (name "Net-(D1-K)") (class "Default")
      (node (ref "D1") (pin "1") (pinfunction "K_1") (pintype "passive"))
      (node (ref "D2") (pin "1") (pinfunction "K_1") (pintype "passive"))
      (node (ref "P4") (pin "1") (pinfunction "1_1") (pintype "passive"))
    )
    (net (code "47") (name "Net-(D2-A)") (class "Default")
      (node (ref "D2") (pin "2") (pinfunction "A_2") (pintype "passive"))
      (node (ref "SW1") (pin "1") (pinfunction "1_1") (pintype "passive"))
    )
    (net (code "48") (name "Net-(D3-K)") (class "Default")
      (node (ref "D3") (pin "1") (pinfunction "K_1") (pintype "passive"))
      (node (ref "P7") (pin "1") (pinfunction "1_1") (pintype "passive"))
    )
    (net (code "49") (name "Net-(L1-Pad1)") (class "Default")
      (node (ref "L1") (pin "1") (pinfunction "1_1") (pintype "passive"))
      (node (ref "SW1") (pin "2") (pinfunction "2_2") (pintype "passive"))
    )
    (net (code "50") (name "Net-(LED1-Pad2)") (class "Default")
      (node (ref "LED1") (pin "2") (pinfunction "2_2") (pintype "passive"))
      (node (ref "R10") (pin "1") (pinfunction "1_1") (pintype "passive"))
    )
    (net (code "51") (name "Net-(LED2-Pad2)") (class "Default")
      (node (ref "LED2") (pin "2") (pinfunction "2_2") (pintype "passive"))
      (node (ref "R11") (pin "1") (pinfunction "1_1") (pintype "passive"))
    )
    (net (code "52") (name "Net-(LED3-Pad2)") (class "Default")
      (node (ref "LED3") (pin "2") (pinfunction "2_2") (pintype "passive"))
      (node (ref "R12") (pin "1") (pinfunction "1_1") (pintype "passive"))
    )
    (net (code "53") (name "Net-(LED4-Pad2)") (class "Default")
      (node (ref "LED4") (pin "2") (pinfunction "2_2") (pintype "passive"))
      (node (ref "R13") (pin "1") (pinfunction "1_1") (pintype "passive"))
    )
    (net (code "54") (name "Net-(LED5-Pad2)") (class "Default")
      (node (ref "LED5") (pin "2") (pinfunction "2_2") (pintype "passive"))
      (node (ref "R14") (pin "1") (pinfunction "1_1") (pintype "passive"))
    )
    (net (code "55") (name "Net-(R5-Pad1)") (class "Default")
      (node (ref "R5") (pin "1") (pinfunction "1_1") (pintype "passive"))
      (node (ref "S6") (pin "1") (pinfunction "1_1") (pintype "passive"))
    )
    (net (code "56") (name "Net-(U1-~{HIB})") (class "Default")
      (node (ref "P1") (pin "1") (pinfunction "1_1") (pintype "passive"))
      (node (ref "U1") (pin "33") (pinfunction "~{HIB}_33") (pintype "passive"))
    )
    (net (code "57") (name "Net-(U1-~{WAKE})") (class "Default")
      (node (ref "R3") (pin "2") (pinfunction "2_2") (pintype "passive"))
      (node (ref "S1") (pin "2") (pinfunction "2_2") (pintype "passive"))
      (node (ref "U1") (pin "32") (pinfunction "~{WAKE}_32") (pintype "passive"))
    )
    (net (code "58") (name "Net-(U2-B)") (class "Default")
      (node (ref "R2") (pin "2") (pinfunction "2_2") (pintype "passive"))
      (node (ref "U2") (pin "1") (pinfunction "B_1") (pintype "passive"))
    )
    (net (code "59") (name "Net-(U2-C)") (class "Default")
      (node (ref "LS1") (pin "1") (pinfunction "1_1") (pintype "passive"))
      (node (ref "U2") (pin "3") (pinfunction "C_3") (pintype "passive"))
    )
    (net (code "60") (name "OSC0") (class "Default")
      (node (ref "C2") (pin "2") (pinfunction "2_2") (pintype "passive"))
      (node (ref "U1") (pin "40") (pinfunction "OSC0_40") (pintype "passive"))
      (node (ref "X1") (pin "2") (pinfunction "2_2") (pintype "passive"))
    )
    (net (code "61") (name "OSC1") (class "Default")
      (node (ref "R1") (pin "1") (pinfunction "1_1") (pintype "passive"))
      (node (ref "U1") (pin "41") (pinfunction "OSC1_41") (pintype "passive"))
    )
    (net (code "62") (name "RESET") (class "Default")
      (node (ref "C5") (pin "1") (pinfunction "1_1") (pintype "passive"))
      (node (ref "HD1") (pin "5") (pinfunction "5_5") (pintype "passive"))
      (node (ref "R4") (pin "1") (pinfunction "1_1") (pintype "passive"))
      (node (ref "R5") (pin "2") (pinfunction "2_2") (pintype "passive"))
      (node (ref "U1") (pin "38") (pinfunction "~{RST}_38") (pintype "passive"))
    )
    (net (code "63") (name "SW1") (class "Default")
      (node (ref "S2") (pin "2") (pinfunction "2_2") (pintype "passive"))
      (node (ref "U1") (pin "28") (pinfunction "PF0_28") (pintype "bidirectional"))
    )
    (net (code "64") (name "SW2") (class "Default")
      (node (ref "S3") (pin "2") (pinfunction "2_2") (pintype "passive"))
      (node (ref "U1") (pin "29") (pinfunction "PF1_29") (pintype "bidirectional"))
    )
    (net (code "65") (name "SW3") (class "Default")
      (node (ref "S4") (pin "2") (pinfunction "2_2") (pintype "passive"))
      (node (ref "U1") (pin "30") (pinfunction "PF2_30") (pintype "bidirectional"))
    )
    (net (code "66") (name "SW4") (class "Default")
      (node (ref "S5") (pin "2") (pinfunction "2_2") (pintype "passive"))
      (node (ref "U1") (pin "31") (pinfunction "PF3_31") (pintype "bidirectional"))
    )
    (net (code "67") (name "Speaker") (class "Default")
      (node (ref "R2") (pin "1") (pinfunction "1_1") (pintype "passive"))
      (node (ref "U1") (pin "21") (pinfunction "PA4/SSI0Rx_21") (pintype "bidirectional"))
    )
    (net (code "68") (name "VDDC") (class "Default")
      (node (ref "C6") (pin "1") (pinfunction "1_1") (pintype "passive"))
      (node (ref "C7") (pin "1") (pinfunction "1_1") (pintype "passive"))
      (node (ref "U1") (pin "25") (pinfunction "VDDC_25") (pintype "power_in"))
      (node (ref "U1") (pin "56") (pinfunction "VDDC_56") (pintype "power_in"))
    )
    (net (code "69") (name "VIN") (class "Default")
      (node (ref "C10") (pin "2") (pinfunction "2_2") (pintype "passive"))
      (node (ref "C21") (pin "2") (pinfunction "2_2") (pintype "passive"))
      (node (ref "C24") (pin "2") (pinfunction "2_2") (pintype "passive"))
      (node (ref "C8") (pin "1") (pinfunction "+_1") (pintype "passive"))
      (node (ref "HD13") (pin "1") (pinfunction "1_1") (pintype "passive"))
      (node (ref "HD13") (pin "2") (pinfunction "2_2") (pintype "passive"))
      (node (ref "IC3") (pin "3") (pinfunction "Vin_3") (pintype "passive"))
      (node (ref "IC4") (pin "3") (pinfunction "Vin_3") (pintype "passive"))
      (node (ref "IC5") (pin "3") (pinfunction "Vin_3") (pintype "passive"))
      (node (ref "L1") (pin "2") (pinfunction "2_2") (pintype "passive"))
    )
    (net (code "70") (name "XOSC0") (class "Default")
      (node (ref "C4") (pin "2") (pinfunction "2_2") (pintype "passive"))
      (node (ref "U1") (pin "34") (pinfunction "XOSC0_34") (pintype "passive"))
      (node (ref "X2") (pin "2") (pinfunction "2_2") (pintype "passive"))
    )
    (net (code "71") (name "XOSC1") (class "Default")
      (node (ref "C3") (pin "1") (pinfunction "1_1") (pintype "passive"))
      (node (ref "U1") (pin "36") (pinfunction "XOSC1_36") (pintype "passive"))
      (node (ref "X2") (pin "1") (pinfunction "1_1") (pintype "passive"))
    )
    (net (code "72") (name "unconnected-(HD3-Pad7)") (class "Default")
      (node (ref "HD3") (pin "7") (pinfunction "7_7") (pintype "passive+no_connect"))
    )
    (net (code "73") (name "unconnected-(HD7-Pad5)") (class "Default")
      (node (ref "HD7") (pin "5") (pinfunction "5_5") (pintype "passive+no_connect"))
    )
    (net (code "74") (name "unconnected-(HD7-Pad6)") (class "Default")
      (node (ref "HD7") (pin "6") (pinfunction "6_6") (pintype "passive+no_connect"))
    )
    (net (code "75") (name "unconnected-(HD7-Pad7)") (class "Default")
      (node (ref "HD7") (pin "7") (pinfunction "7_7") (pintype "passive+no_connect"))
    )
    (net (code "76") (name "unconnected-(HD9-Pad2)") (class "Default")
      (node (ref "HD9") (pin "2") (pinfunction "2_2") (pintype "passive+no_connect"))
    )
    (net (code "77") (name "unconnected-(HD10-Pad2)") (class "Default")
      (node (ref "HD10") (pin "2") (pinfunction "2_2") (pintype "passive+no_connect"))
    )
    (net (code "78") (name "unconnected-(HD11-Pad2)") (class "Default")
      (node (ref "HD11") (pin "2") (pinfunction "2_2") (pintype "passive+no_connect"))
    )
    (net (code "79") (name "unconnected-(HD12-Pad2)") (class "Default")
      (node (ref "HD12") (pin "2") (pinfunction "2_2") (pintype "passive+no_connect"))
    )
  )
)
